# auc_pulser.net
KiCad netlist of a schematic drawn in EAGLE
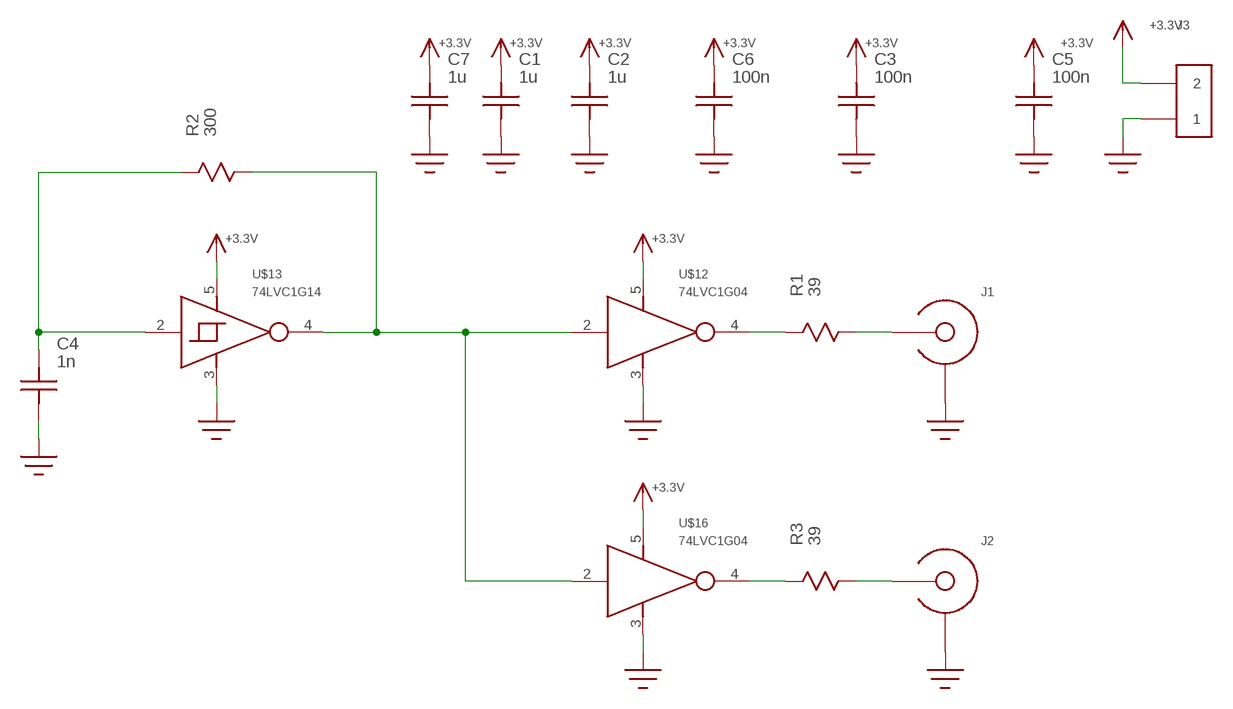
[diagram p0: schematic, sheet 1]

(export (version "E")
  (design (tool "Eeschema 10.0.6"))
  (components
    (comp (ref "C1")
      (value "1u")
      (footprint "eagle-import:0805")
      (libsource (lib "eagle-import") (part "C0805"))
    )
    (comp (ref "C2")
      (value "1u")
      (footprint "eagle-import:0805")
      (libsource (lib "eagle-import") (part "C0805"))
    )
    (comp (ref "C3")
      (value "100n")
      (footprint "eagle-import:C0603")
      (libsource (lib "eagle-import") (part "C0603"))
    )
    (comp (ref "C4")
      (value "1n")
      (footprint "eagle-import:C0603")
      (libsource (lib "eagle-import") (part "C0603"))
    )
    (comp (ref "C5")
      (value "100n")
      (footprint "eagle-import:C0603")
      (libsource (lib "eagle-import") (part "C0603"))
    )
    (comp (ref "C6")
      (value "100n")
      (footprint "eagle-import:C0603")
      (libsource (lib "eagle-import") (part "C0603"))
    )
    (comp (ref "C7")
      (value "1u")
      (footprint "eagle-import:0805")
      (libsource (lib "eagle-import") (part "C0805"))
    )
    (comp (ref "J1")
      (value "BNC_MALE_PCB")
      (footprint "eagle-import:BNC_MALE_PCB")
      (libsource (lib "eagle-import") (part "BNC_MALE_PCB"))
    )
    (comp (ref "J2")
      (value "EDGE_LAUNCH_JACK")
      (footprint "eagle-import:EDGE_LAUNCH_RF_CON")
      (libsource (lib "eagle-import") (part "EDGE_LAUNCH_JACK"))
    )
    (comp (ref "J3")
      (value "HEADER_2PIN")
      (footprint "eagle-import:HEADER_2PIN")
      (libsource (lib "eagle-import") (part "HEADER_2PIN"))
    )
    (comp (ref "R1")
      (value "39")
      (footprint "eagle-import:R0603")
      (libsource (lib "eagle-import") (part "R0603"))
    )
    (comp (ref "R2")
      (value "300")
      (footprint "eagle-import:R0603")
      (libsource (lib "eagle-import") (part "R0603"))
    )
    (comp (ref "R3")
      (value "39")
      (footprint "eagle-import:R0603")
      (libsource (lib "eagle-import") (part "R0603"))
    )
    (comp (ref "U$12")
      (value "74LVC1G04")
      (footprint "eagle-import:SOT23-5")
      (libsource (lib "eagle-import") (part "74LVC1G04"))
    )
    (comp (ref "U$13")
      (value "74LVC1G14")
      (footprint "eagle-import:SOT23-5")
      (libsource (lib "eagle-import") (part "74LVC1G14"))
    )
    (comp (ref "U$16")
      (value "74LVC1G04")
      (footprint "eagle-import:SOT23-5")
      (libsource (lib "eagle-import") (part "74LVC1G04"))
    )
  )
  (nets
    (net (code "1") (name "+3.3V") (class "Default")
      (node (ref "C1") (pin "P$2") (pinfunction "P$2_P$2") (pintype "bidirectional"))
      (node (ref "C2") (pin "P$2") (pinfunction "P$2_P$2") (pintype "bidirectional"))
      (node (ref "C3") (pin "P$2") (pinfunction "P$2_P$2") (pintype "bidirectional"))
      (node (ref "C5") (pin "P$2") (pinfunction "P$2_P$2") (pintype "bidirectional"))
      (node (ref "C6") (pin "P$2") (pinfunction "P$2_P$2") (pintype "bidirectional"))
      (node (ref "C7") (pin "P$2") (pinfunction "P$2_P$2") (pintype "bidirectional"))
      (node (ref "J3") (pin "2") (pinfunction "2_2") (pintype "bidirectional"))
      (node (ref "U$12") (pin "5") (pinfunction "VCC_5") (pintype "bidirectional"))
      (node (ref "U$13") (pin "5") (pinfunction "VCC_5") (pintype "bidirectional"))
      (node (ref "U$16") (pin "5") (pinfunction "VCC_5") (pintype "bidirectional"))
    )
    (net (code "2") (name "GND") (class "Default")
      (node (ref "C1") (pin "P$1") (pinfunction "P$1_P$1") (pintype "bidirectional"))
      (node (ref "C2") (pin "P$1") (pinfunction "P$1_P$1") (pintype "bidirectional"))
      (node (ref "C3") (pin "P$1") (pinfunction "P$1_P$1") (pintype "bidirectional"))
      (node (ref "C4") (pin "P$1") (pinfunction "P$1_P$1") (pintype "bidirectional"))
      (node (ref "C5") (pin "P$1") (pinfunction "P$1_P$1") (pintype "bidirectional"))
      (node (ref "C6") (pin "P$1") (pinfunction "P$1_P$1") (pintype "bidirectional"))
      (node (ref "C7") (pin "P$1") (pinfunction "P$1_P$1") (pintype "bidirectional"))
      (node (ref "J1") (pin "SHIELD@1") (pinfunction "SHIELD_SHIELD@1") (pintype "bidirectional"))
      (node (ref "J1") (pin "SHIELD@2") (pinfunction "SHIELD_SHIELD@2") (pintype "bidirectional"))
      (node (ref "J1") (pin "SHIELD@3") (pinfunction "SHIELD_SHIELD@3") (pintype "bidirectional"))
      (node (ref "J1") (pin "SHIELD@4") (pinfunction "SHIELD_SHIELD@4") (pintype "bidirectional"))
      (node (ref "J2") (pin "GND@1") (pinfunction "SHIELD_GND@1") (pintype "bidirectional"))
      (node (ref "J2") (pin "GND@10") (pinfunction "SHIELD_GND@10") (pintype "bidirectional"))
      (node (ref "J2") (pin "GND@11") (pinfunction "SHIELD_GND@11") (pintype "bidirectional"))
      (node (ref "J2") (pin "GND@12") (pinfunction "SHIELD_GND@12") (pintype "bidirectional"))
      (node (ref "J2") (pin "GND@2") (pinfunction "SHIELD_GND@2") (pintype "bidirectional"))
      (node (ref "J2") (pin "GND@3") (pinfunction "SHIELD_GND@3") (pintype "bidirectional"))
      (node (ref "J2") (pin "GND@4") (pinfunction "SHIELD_GND@4") (pintype "bidirectional"))
      (node (ref "J2") (pin "GND@5") (pinfunction "SHIELD_GND@5") (pintype "bidirectional"))
      (node (ref "J2") (pin "GND@6") (pinfunction "SHIELD_GND@6") (pintype "bidirectional"))
      (node (ref "J2") (pin "GND@7") (pinfunction "SHIELD_GND@7") (pintype "bidirectional"))
      (node (ref "J2") (pin "GND@8") (pinfunction "SHIELD_GND@8") (pintype "bidirectional"))
      (node (ref "J2") (pin "GND@9") (pinfunction "SHIELD_GND@9") (pintype "bidirectional"))
      (node (ref "J2") (pin "SHIELD@1") (pinfunction "SHIELD_SHIELD@1") (pintype "bidirectional"))
      (node (ref "J2") (pin "SHIELD@2") (pinfunction "SHIELD_SHIELD@2") (pintype "bidirectional"))
      (node (ref "J3") (pin "1") (pinfunction "1_1") (pintype "bidirectional"))
      (node (ref "U$12") (pin "3") (pinfunction "GND_3") (pintype "bidirectional"))
      (node (ref "U$13") (pin "3") (pinfunction "GND_3") (pintype "bidirectional"))
      (node (ref "U$16") (pin "3") (pinfunction "GND_3") (pintype "bidirectional"))
    )
    (net (code "3") (name "Net-(R1-P$3)") (class "Default")
      (node (ref "R1") (pin "P$1") (pinfunction "P$3_P$1") (pintype "bidirectional"))
      (node (ref "U$12") (pin "4") (pinfunction "OUT_4") (pintype "bidirectional"))
    )
    (net (code "4") (name "Net-(R1-P$4)") (class "Default")
      (node (ref "J1") (pin "CENTER") (pinfunction "CENTER_CENTER") (pintype "bidirectional"))
      (node (ref "R1") (pin "P$2") (pinfunction "P$4_P$2") (pintype "bidirectional"))
    )
    (net (code "5") (name "Net-(R2-P$3)") (class "Default")
      (node (ref "C4") (pin "P$2") (pinfunction "P$2_P$2") (pintype "bidirectional"))
      (node (ref "R2") (pin "P$1") (pinfunction "P$3_P$1") (pintype "bidirectional"))
      (node (ref "U$13") (pin "2") (pinfunction "IN_2") (pintype "bidirectional"))
    )
    (net (code "6") (name "Net-(R2-P$4)") (class "Default")
      (node (ref "R2") (pin "P$2") (pinfunction "P$4_P$2") (pintype "bidirectional"))
      (node (ref "U$12") (pin "2") (pinfunction "IN_2") (pintype "bidirectional"))
      (node (ref "U$13") (pin "4") (pinfunction "OUT_4") (pintype "bidirectional"))
      (node (ref "U$16") (pin "2") (pinfunction "IN_2") (pintype "bidirectional"))
    )
    (net (code "7") (name "Net-(R3-P$3)") (class "Default")
      (node (ref "R3") (pin "P$1") (pinfunction "P$3_P$1") (pintype "bidirectional"))
      (node (ref "U$16") (pin "4") (pinfunction "OUT_4") (pintype "bidirectional"))
    )
    (net (code "8") (name "Net-(R3-P$4)") (class "Default")
      (node (ref "J2") (pin "CENTER") (pinfunction "CENTER_CENTER") (pintype "bidirectional"))
      (node (ref "R3") (pin "P$2") (pinfunction "P$4_P$2") (pintype "bidirectional"))
    )
  )
)
